# WSN_Gateway_feather_v2.net
KiCad netlist of a schematic drawn in EAGLE
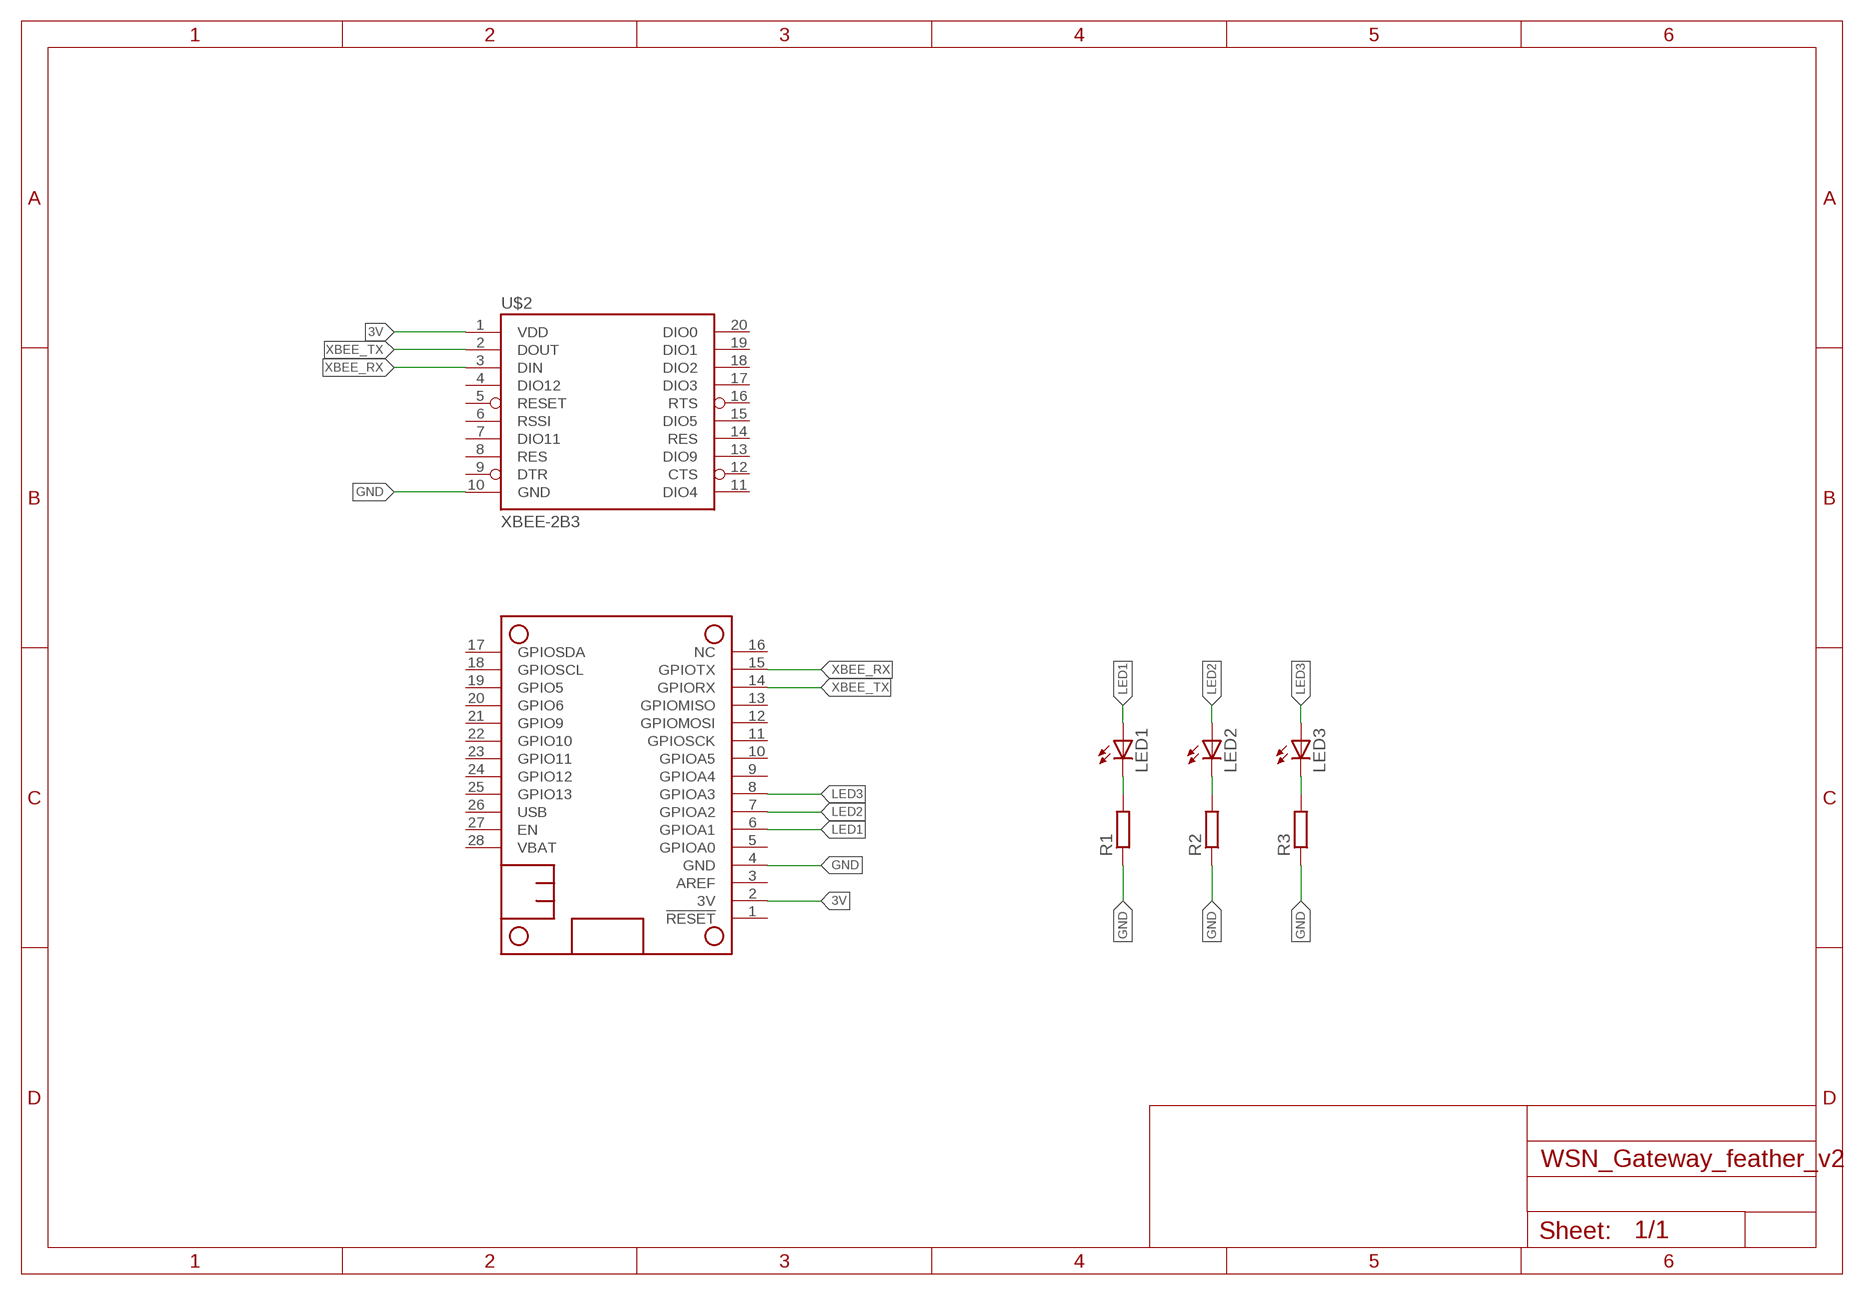
[diagram p0: schematic, sheet 1]

(export (version "E")
  (design (tool "Eeschema 10.0.6"))
  (components
    (comp (ref "LED1")
      (value "LEDCHIPLED_0805")
      (footprint "eagle-import:CHIPLED_0805")
      (libsource (lib "eagle-import") (part "LEDCHIPLED_0805"))
    )
    (comp (ref "LED2")
      (value "LEDCHIPLED_0805")
      (footprint "eagle-import:CHIPLED_0805")
      (libsource (lib "eagle-import") (part "LEDCHIPLED_0805"))
    )
    (comp (ref "LED3")
      (value "LEDCHIPLED_0805")
      (footprint "eagle-import:CHIPLED_0805")
      (libsource (lib "eagle-import") (part "LEDCHIPLED_0805"))
    )
    (comp (ref "MS1")
      (value "FEATHERWING_NODIM_NOHOLES")
      (footprint "eagle-import:FEATHERWING_DIM_2")
      (libsource (lib "eagle-import") (part "FEATHERWING_NODIM_NOHOLES"))
    )
    (comp (ref "R1")
      (value "R-EU_R0805")
      (footprint "eagle-import:R0805")
      (libsource (lib "eagle-import") (part "R-EU_R0805"))
    )
    (comp (ref "R2")
      (value "R-EU_R0805")
      (footprint "eagle-import:R0805")
      (libsource (lib "eagle-import") (part "R-EU_R0805"))
    )
    (comp (ref "R3")
      (value "R-EU_R0805")
      (footprint "eagle-import:R0805")
      (libsource (lib "eagle-import") (part "R-EU_R0805"))
    )
    (comp (ref "U$2")
      (value "XBEE-2B3")
      (footprint "eagle-import:XBEE-SMD")
      (libsource (lib "eagle-import") (part "XBEE-2B3"))
    )
  )
  (nets
    (net (code "1") (name "/USB") (class "Default")
      (node (ref "MS1") (pin "26") (pinfunction "USB_26") (pintype "power_in"))
    )
    (net (code "2") (name "/VBAT") (class "Default")
      (node (ref "MS1") (pin "28") (pinfunction "VBAT_28") (pintype "power_in"))
    )
    (net (code "3") (name "3V") (class "Default")
      (node (ref "MS1") (pin "2") (pinfunction "3V_2") (pintype "power_in"))
      (node (ref "U$2") (pin "1") (pinfunction "VDD_1") (pintype "power_in"))
    )
    (net (code "4") (name "GND") (class "Default")
      (node (ref "MS1") (pin "4") (pinfunction "GND_4") (pintype "power_in"))
      (node (ref "R1") (pin "1") (pinfunction "1_1") (pintype "passive"))
      (node (ref "R2") (pin "1") (pinfunction "1_1") (pintype "passive"))
      (node (ref "R3") (pin "1") (pinfunction "1_1") (pintype "passive"))
      (node (ref "U$2") (pin "10") (pinfunction "GND_10") (pintype "power_in"))
    )
    (net (code "5") (name "LED1") (class "Default")
      (node (ref "LED1") (pin "A") (pinfunction "A_A") (pintype "passive"))
      (node (ref "MS1") (pin "6") (pinfunction "GPIOA1_6") (pintype "bidirectional"))
    )
    (net (code "6") (name "LED2") (class "Default")
      (node (ref "LED2") (pin "A") (pinfunction "A_A") (pintype "passive"))
      (node (ref "MS1") (pin "7") (pinfunction "GPIOA2_7") (pintype "bidirectional"))
    )
    (net (code "7") (name "LED3") (class "Default")
      (node (ref "LED3") (pin "A") (pinfunction "A_A") (pintype "passive"))
      (node (ref "MS1") (pin "8") (pinfunction "GPIOA3_8") (pintype "bidirectional"))
    )
    (net (code "8") (name "Net-(LED1-PadC)") (class "Default")
      (node (ref "LED1") (pin "C") (pinfunction "C_C") (pintype "passive"))
      (node (ref "R1") (pin "2") (pinfunction "2_2") (pintype "passive"))
    )
    (net (code "9") (name "Net-(LED2-PadC)") (class "Default")
      (node (ref "LED2") (pin "C") (pinfunction "C_C") (pintype "passive"))
      (node (ref "R2") (pin "2") (pinfunction "2_2") (pintype "passive"))
    )
    (net (code "10") (name "Net-(LED3-PadC)") (class "Default")
      (node (ref "LED3") (pin "C") (pinfunction "C_C") (pintype "passive"))
      (node (ref "R3") (pin "2") (pinfunction "2_2") (pintype "passive"))
    )
    (net (code "11") (name "XBEE_RX") (class "Default")
      (node (ref "MS1") (pin "15") (pinfunction "GPIOTX_15") (pintype "bidirectional"))
      (node (ref "U$2") (pin "3") (pinfunction "DIN_3") (pintype "input"))
    )
    (net (code "12") (name "XBEE_TX") (class "Default")
      (node (ref "MS1") (pin "14") (pinfunction "GPIORX_14") (pintype "bidirectional"))
      (node (ref "U$2") (pin "2") (pinfunction "DOUT_2") (pintype "output"))
    )
    (net (code "13") (name "unconnected-(MS1-AREF-Pad3)") (class "Default")
      (node (ref "MS1") (pin "3") (pinfunction "AREF_3") (pintype "passive"))
    )
    (net (code "14") (name "unconnected-(MS1-EN-Pad27)") (class "Default")
      (node (ref "MS1") (pin "27") (pinfunction "EN_27") (pintype "passive"))
    )
    (net (code "15") (name "unconnected-(MS1-GPIO5-Pad19)") (class "Default")
      (node (ref "MS1") (pin "19") (pinfunction "GPIO5_19") (pintype "bidirectional"))
    )
    (net (code "16") (name "unconnected-(MS1-GPIO6-Pad20)") (class "Default")
      (node (ref "MS1") (pin "20") (pinfunction "GPIO6_20") (pintype "bidirectional"))
    )
    (net (code "17") (name "unconnected-(MS1-GPIO9-Pad21)") (class "Default")
      (node (ref "MS1") (pin "21") (pinfunction "GPIO9_21") (pintype "bidirectional"))
    )
    (net (code "18") (name "unconnected-(MS1-GPIO10-Pad22)") (class "Default")
      (node (ref "MS1") (pin "22") (pinfunction "GPIO10_22") (pintype "bidirectional"))
    )
    (net (code "19") (name "unconnected-(MS1-GPIO11-Pad23)") (class "Default")
      (node (ref "MS1") (pin "23") (pinfunction "GPIO11_23") (pintype "bidirectional"))
    )
    (net (code "20") (name "unconnected-(MS1-GPIO12-Pad24)") (class "Default")
      (node (ref "MS1") (pin "24") (pinfunction "GPIO12_24") (pintype "bidirectional"))
    )
    (net (code "21") (name "unconnected-(MS1-GPIO13-Pad25)") (class "Default")
      (node (ref "MS1") (pin "25") (pinfunction "GPIO13_25") (pintype "bidirectional"))
    )
    (net (code "22") (name "unconnected-(MS1-GPIOA0-Pad5)") (class "Default")
      (node (ref "MS1") (pin "5") (pinfunction "GPIOA0_5") (pintype "bidirectional"))
    )
    (net (code "23") (name "unconnected-(MS1-GPIOA4-Pad9)") (class "Default")
      (node (ref "MS1") (pin "9") (pinfunction "GPIOA4_9") (pintype "bidirectional"))
    )
    (net (code "24") (name "unconnected-(MS1-GPIOA5-Pad10)") (class "Default")
      (node (ref "MS1") (pin "10") (pinfunction "GPIOA5_10") (pintype "bidirectional"))
    )
    (net (code "25") (name "unconnected-(MS1-GPIOMISO-Pad13)") (class "Default")
      (node (ref "MS1") (pin "13") (pinfunction "GPIOMISO_13") (pintype "bidirectional"))
    )
    (net (code "26") (name "unconnected-(MS1-GPIOMOSI-Pad12)") (class "Default")
      (node (ref "MS1") (pin "12") (pinfunction "GPIOMOSI_12") (pintype "bidirectional"))
    )
    (net (code "27") (name "unconnected-(MS1-GPIOSCK-Pad11)") (class "Default")
      (node (ref "MS1") (pin "11") (pinfunction "GPIOSCK_11") (pintype "bidirectional"))
    )
    (net (code "28") (name "unconnected-(MS1-GPIOSCL-Pad18)") (class "Default")
      (node (ref "MS1") (pin "18") (pinfunction "GPIOSCL_18") (pintype "bidirectional"))
    )
    (net (code "29") (name "unconnected-(MS1-GPIOSDA-Pad17)") (class "Default")
      (node (ref "MS1") (pin "17") (pinfunction "GPIOSDA_17") (pintype "bidirectional"))
    )
    (net (code "30") (name "unconnected-(MS1-NC-Pad16)") (class "Default")
      (node (ref "MS1") (pin "16") (pinfunction "NC_16") (pintype "passive"))
    )
    (net (code "31") (name "unconnected-(MS1-~{RESET}-Pad1)") (class "Default")
      (node (ref "MS1") (pin "1") (pinfunction "~{RESET}_1") (pintype "input"))
    )
    (net (code "32") (name "unconnected-(U$2-CTS-Pad12)") (class "Default")
      (node (ref "U$2") (pin "12") (pinfunction "CTS_12") (pintype "output"))
    )
    (net (code "33") (name "unconnected-(U$2-DIO0-Pad20)") (class "Default")
      (node (ref "U$2") (pin "20") (pinfunction "DIO0_20") (pintype "bidirectional"))
    )
    (net (code "34") (name "unconnected-(U$2-DIO1-Pad19)") (class "Default")
      (node (ref "U$2") (pin "19") (pinfunction "DIO1_19") (pintype "bidirectional"))
    )
    (net (code "35") (name "unconnected-(U$2-DIO2-Pad18)") (class "Default")
      (node (ref "U$2") (pin "18") (pinfunction "DIO2_18") (pintype "bidirectional"))
    )
    (net (code "36") (name "unconnected-(U$2-DIO3-Pad17)") (class "Default")
      (node (ref "U$2") (pin "17") (pinfunction "DIO3_17") (pintype "bidirectional"))
    )
    (net (code "37") (name "unconnected-(U$2-DIO4-Pad11)") (class "Default")
      (node (ref "U$2") (pin "11") (pinfunction "DIO4_11") (pintype "bidirectional"))
    )
    (net (code "38") (name "unconnected-(U$2-DIO5-Pad15)") (class "Default")
      (node (ref "U$2") (pin "15") (pinfunction "DIO5_15") (pintype "bidirectional"))
    )
    (net (code "39") (name "unconnected-(U$2-DIO9-Pad13)") (class "Default")
      (node (ref "U$2") (pin "13") (pinfunction "DIO9_13") (pintype "bidirectional"))
    )
    (net (code "40") (name "unconnected-(U$2-DIO11-Pad7)") (class "Default")
      (node (ref "U$2") (pin "7") (pinfunction "DIO11_7") (pintype "bidirectional"))
    )
    (net (code "41") (name "unconnected-(U$2-DIO12-Pad4)") (class "Default")
      (node (ref "U$2") (pin "4") (pinfunction "DIO12_4") (pintype "bidirectional"))
    )
    (net (code "42") (name "unconnected-(U$2-DTR-Pad9)") (class "Default")
      (node (ref "U$2") (pin "9") (pinfunction "DTR_9") (pintype "bidirectional"))
    )
    (net (code "43") (name "unconnected-(U$2-RES-Pad8)") (class "Default")
      (node (ref "U$2") (pin "8") (pinfunction "RES_8") (pintype "bidirectional"))
    )
    (net (code "44") (name "unconnected-(U$2-RES-Pad14)") (class "Default")
      (node (ref "U$2") (pin "14") (pinfunction "RES_14") (pintype "bidirectional"))
    )
    (net (code "45") (name "unconnected-(U$2-RESET-Pad5)") (class "Default")
      (node (ref "U$2") (pin "5") (pinfunction "RESET_5") (pintype "input"))
    )
    (net (code "46") (name "unconnected-(U$2-RSSI-Pad6)") (class "Default")
      (node (ref "U$2") (pin "6") (pinfunction "RSSI_6") (pintype "bidirectional"))
    )
    (net (code "47") (name "unconnected-(U$2-RTS-Pad16)") (class "Default")
      (node (ref "U$2") (pin "16") (pinfunction "RTS_16") (pintype "input"))
    )
  )
)
